# 2_-_Connector_Page.net
KiCad netlist of a schematic drawn in Altium Designer
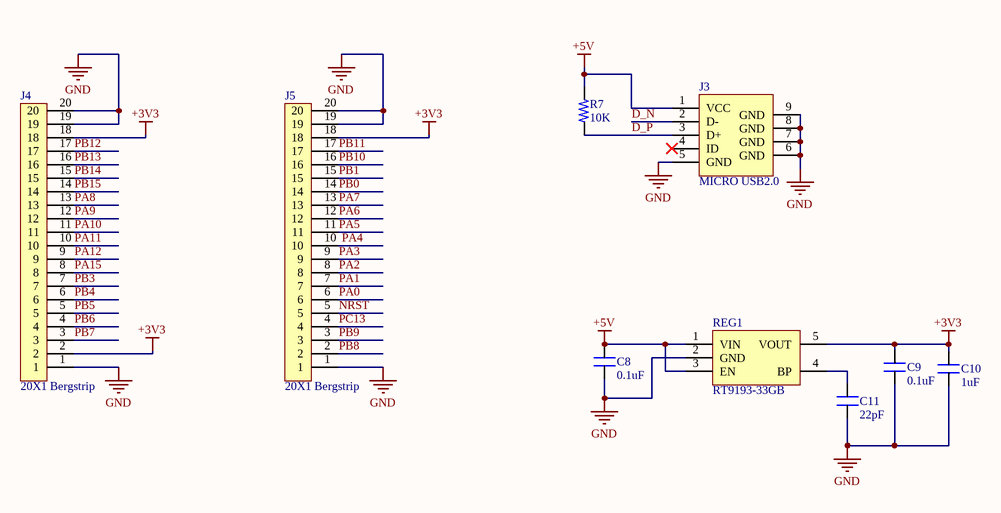
[diagram p0: [2]- Connector_Page.SchDoc]

(export (version "E")
  (design (tool "Eeschema 10.0.6"))
  (components
    (comp (ref "C8")
      (value "0.1uF")
      (footprint "CAP_0805")
      (description "0.1µF ±5% 50V Ceramic Capacitor X7R 0805 (2012 Metric)")
      (fields
        (field (name "MANUFACTURER") "KEMET")
        (field (name "MANUFACTURING PART NUMBER") "C0805C104J5RACTU")
      )
      (libsource (lib "STM_SCH_LIB") (part "CAP_0.1uF-50V-5%-0805"))
    )
    (comp (ref "C9")
      (value "0.1uF")
      (footprint "CAP_0805")
      (description "0.1µF ±5% 50V Ceramic Capacitor X7R 0805 (2012 Metric)")
      (fields
        (field (name "MANUFACTURER") "KEMET")
        (field (name "MANUFACTURING PART NUMBER") "C0805C104J5RACTU")
      )
      (libsource (lib "STM_SCH_LIB") (part "CAP_0.1uF-50V-5%-0805"))
    )
    (comp (ref "C10")
      (value "1uF")
      (footprint "CAP_0805")
      (description "1µF ±5% 50V Ceramic Capacitor X7R 0805 (2012 Metric)")
      (fields
        (field (name "MANUFACTURER") "Yageo")
        (field (name "MANUFACTURING PART NUMBER") "CC0805JKX7R9BB105")
      )
      (libsource (lib "STM_SCH_LIB") (part "CAP_1uF-50V-5%-0805"))
    )
    (comp (ref "C11")
      (value "22pF")
      (footprint "CAP_0805")
      (description "22pF ±5% 50V Ceramic Capacitor C0G, NP0 0805 (2012 Metric)")
      (fields
        (field (name "MANUFACTURER") "KEMET")
        (field (name "MANUFACTURER PART NUMBER") "C0805C220J5GACTU")
      )
      (libsource (lib "STM_SCH_LIB") (part "CAP_22pF-50V-5%-0805"))
    )
    (comp (ref "J3")
      (value "MICRO USB2.0")
      (footprint "CON_10118192-0001LF_SMD")
      (description "USB - micro B USB 2.0 Receptacle Connector 5 Position Surface Mount, Right Angle")
      (fields
        (field (name "MANUFACTURER") "Amphenol ICC (FCI)")
        (field (name "MANUFACTURING PART NUMBER") "10118192-0002LF")
      )
      (libsource (lib "STM_SCH_LIB") (part "CON-USB_10118192-0002LF-SMD"))
    )
    (comp (ref "J4")
      (value "20X1 Bergstrip")
      (footprint "CON20_100_40D72_TH_ST")
      (description "20 pin, 1 row, 2.54mm pitch bergstrip")
      (fields (field (name "MANUFACTURER") "NA"))
      (libsource (lib "STM_SCH_LIB") (part "CON-BS-PLG_20X1-100-TH-ST"))
    )
    (comp (ref "J5")
      (value "20X1 Bergstrip")
      (footprint "CON20_100_40D72_TH_ST")
      (description "20 pin, 1 row, 2.54mm pitch bergstrip")
      (fields (field (name "MANUFACTURER") "NA"))
      (libsource (lib "STM_SCH_LIB") (part "CON-BS-PLG_20X1-100-TH-ST"))
    )
    (comp (ref "R7")
      (value "10K")
      (footprint "RES_0805")
      (description "10 kOhms ±1% 0.125W, 1/8W Chip Resistor 0805 (2012 Metric) Moisture Resistant Thick Film")
      (fields
        (field (name "MANUFACTURER") "Yageo")
        (field (name "MANUFACTURING PART NUMBER") "RC0805FR-0710KL")
      )
      (libsource (lib "STM_INT_LIB") (part "RES_10K-0.125W-1%-0805"))
    )
    (comp (ref "REG1")
      (value "RT9193-33GB")
      (footprint "SOT23-5")
      (description "Linear Voltage Regulator IC 1 Output 300mA SOT-23-5")
      (fields (field (name "MANUFACTURER") "Richtek USA Inc."))
      (libsource (lib "STM_SCH_LIB") (part "REG_3.3V-5.5V-0.3A-SOT-23-5"))
    )
  )
  (nets
    (net (code "1") (name "+3V3") (class "Default")
      (node (ref "C10") (pin "2") (pinfunction "2_2") (pintype "passive"))
      (node (ref "C9") (pin "2") (pinfunction "2_2") (pintype "passive"))
      (node (ref "J4") (pin "18") (pinfunction "18_18") (pintype "passive"))
      (node (ref "J4") (pin "2") (pinfunction "2_2") (pintype "passive"))
      (node (ref "J5") (pin "18") (pinfunction "18_18") (pintype "passive"))
      (node (ref "REG1") (pin "5") (pinfunction "VOUT_5") (pintype "passive"))
    )
    (net (code "2") (name "+5V") (class "Default")
      (node (ref "C8") (pin "2") (pinfunction "2_2") (pintype "passive"))
      (node (ref "J3") (pin "1") (pinfunction "VCC_1") (pintype "passive"))
      (node (ref "R7") (pin "2") (pinfunction "2_2") (pintype "passive"))
      (node (ref "REG1") (pin "1") (pinfunction "VIN_1") (pintype "passive"))
      (node (ref "REG1") (pin "3") (pinfunction "EN_3") (pintype "passive"))
    )
    (net (code "3") (name "/D_N") (class "Default")
      (node (ref "J3") (pin "2") (pinfunction "D-_2") (pintype "passive"))
    )
    (net (code "4") (name "/D_P") (class "Default")
      (node (ref "J3") (pin "3") (pinfunction "D+_3") (pintype "passive"))
      (node (ref "R7") (pin "1") (pinfunction "1_1") (pintype "passive"))
    )
    (net (code "5") (name "/NRST") (class "Default")
      (node (ref "J5") (pin "5") (pinfunction "5_5") (pintype "passive"))
    )
    (net (code "6") (name "/PA0") (class "Default")
      (node (ref "J5") (pin "6") (pinfunction "6_6") (pintype "passive"))
    )
    (net (code "7") (name "/PA1") (class "Default")
      (node (ref "J5") (pin "7") (pinfunction "7_7") (pintype "passive"))
    )
    (net (code "8") (name "/PA2") (class "Default")
      (node (ref "J5") (pin "8") (pinfunction "8_8") (pintype "passive"))
    )
    (net (code "9") (name "/PA3") (class "Default")
      (node (ref "J5") (pin "9") (pinfunction "9_9") (pintype "passive"))
    )
    (net (code "10") (name "/PA4") (class "Default")
      (node (ref "J5") (pin "10") (pinfunction "10_10") (pintype "passive"))
    )
    (net (code "11") (name "/PA5") (class "Default")
      (node (ref "J5") (pin "11") (pinfunction "11_11") (pintype "passive"))
    )
    (net (code "12") (name "/PA6") (class "Default")
      (node (ref "J5") (pin "12") (pinfunction "12_12") (pintype "passive"))
    )
    (net (code "13") (name "/PA7") (class "Default")
      (node (ref "J5") (pin "13") (pinfunction "13_13") (pintype "passive"))
    )
    (net (code "14") (name "/PA8") (class "Default")
      (node (ref "J4") (pin "13") (pinfunction "13_13") (pintype "passive"))
    )
    (net (code "15") (name "/PA9") (class "Default")
      (node (ref "J4") (pin "12") (pinfunction "12_12") (pintype "passive"))
    )
    (net (code "16") (name "/PA10") (class "Default")
      (node (ref "J4") (pin "11") (pinfunction "11_11") (pintype "passive"))
    )
    (net (code "17") (name "/PA11") (class "Default")
      (node (ref "J4") (pin "10") (pinfunction "10_10") (pintype "passive"))
    )
    (net (code "18") (name "/PA12") (class "Default")
      (node (ref "J4") (pin "9") (pinfunction "9_9") (pintype "passive"))
    )
    (net (code "19") (name "/PA15") (class "Default")
      (node (ref "J4") (pin "8") (pinfunction "8_8") (pintype "passive"))
    )
    (net (code "20") (name "/PB0") (class "Default")
      (node (ref "J5") (pin "14") (pinfunction "14_14") (pintype "passive"))
    )
    (net (code "21") (name "/PB1") (class "Default")
      (node (ref "J5") (pin "15") (pinfunction "15_15") (pintype "passive"))
    )
    (net (code "22") (name "/PB3") (class "Default")
      (node (ref "J4") (pin "7") (pinfunction "7_7") (pintype "passive"))
    )
    (net (code "23") (name "/PB4") (class "Default")
      (node (ref "J4") (pin "6") (pinfunction "6_6") (pintype "passive"))
    )
    (net (code "24") (name "/PB5") (class "Default")
      (node (ref "J4") (pin "5") (pinfunction "5_5") (pintype "passive"))
    )
    (net (code "25") (name "/PB6") (class "Default")
      (node (ref "J4") (pin "4") (pinfunction "4_4") (pintype "passive"))
    )
    (net (code "26") (name "/PB7") (class "Default")
      (node (ref "J4") (pin "3") (pinfunction "3_3") (pintype "passive"))
    )
    (net (code "27") (name "/PB8") (class "Default")
      (node (ref "J5") (pin "2") (pinfunction "2_2") (pintype "passive"))
    )
    (net (code "28") (name "/PB9") (class "Default")
      (node (ref "J5") (pin "3") (pinfunction "3_3") (pintype "passive"))
    )
    (net (code "29") (name "/PB10") (class "Default")
      (node (ref "J5") (pin "16") (pinfunction "16_16") (pintype "passive"))
    )
    (net (code "30") (name "/PB11") (class "Default")
      (node (ref "J5") (pin "17") (pinfunction "17_17") (pintype "passive"))
    )
    (net (code "31") (name "/PB12") (class "Default")
      (node (ref "J4") (pin "17") (pinfunction "17_17") (pintype "passive"))
    )
    (net (code "32") (name "/PB13") (class "Default")
      (node (ref "J4") (pin "16") (pinfunction "16_16") (pintype "passive"))
    )
    (net (code "33") (name "/PB14") (class "Default")
      (node (ref "J4") (pin "15") (pinfunction "15_15") (pintype "passive"))
    )
    (net (code "34") (name "/PB15") (class "Default")
      (node (ref "J4") (pin "14") (pinfunction "14_14") (pintype "passive"))
    )
    (net (code "35") (name "/PC13") (class "Default")
      (node (ref "J5") (pin "4") (pinfunction "4_4") (pintype "passive"))
    )
    (net (code "36") (name "GND") (class "Default")
      (node (ref "C10") (pin "1") (pinfunction "1_1") (pintype "passive"))
      (node (ref "C11") (pin "1") (pinfunction "1_1") (pintype "passive"))
      (node (ref "C8") (pin "1") (pinfunction "1_1") (pintype "passive"))
      (node (ref "C9") (pin "1") (pinfunction "1_1") (pintype "passive"))
      (node (ref "J3") (pin "5") (pinfunction "GND_5") (pintype "passive"))
      (node (ref "J3") (pin "6") (pinfunction "GND_6") (pintype "passive"))
      (node (ref "J3") (pin "7") (pinfunction "GND_7") (pintype "passive"))
      (node (ref "J3") (pin "8") (pinfunction "GND_8") (pintype "passive"))
      (node (ref "J3") (pin "9") (pinfunction "GND_9") (pintype "passive"))
      (node (ref "J4") (pin "1") (pinfunction "1_1") (pintype "passive"))
      (node (ref "J4") (pin "19") (pinfunction "19_19") (pintype "passive"))
      (node (ref "J4") (pin "20") (pinfunction "20_20") (pintype "passive"))
      (node (ref "J5") (pin "1") (pinfunction "1_1") (pintype "passive"))
      (node (ref "J5") (pin "19") (pinfunction "19_19") (pintype "passive"))
      (node (ref "J5") (pin "20") (pinfunction "20_20") (pintype "passive"))
      (node (ref "REG1") (pin "2") (pinfunction "GND_2") (pintype "passive"))
    )
    (net (code "37") (name "Net-(REG1-BP)") (class "Default")
      (node (ref "C11") (pin "2") (pinfunction "2_2") (pintype "passive"))
      (node (ref "REG1") (pin "4") (pinfunction "BP_4") (pintype "passive"))
    )
    (net (code "38") (name "unconnected-(J3-ID-Pad4)") (class "Default")
      (node (ref "J3") (pin "4") (pinfunction "ID_4") (pintype "passive+no_connect"))
    )
  )
)
